# auto-discharge.net
KiCad netlist of a schematic drawn in Altium Designer
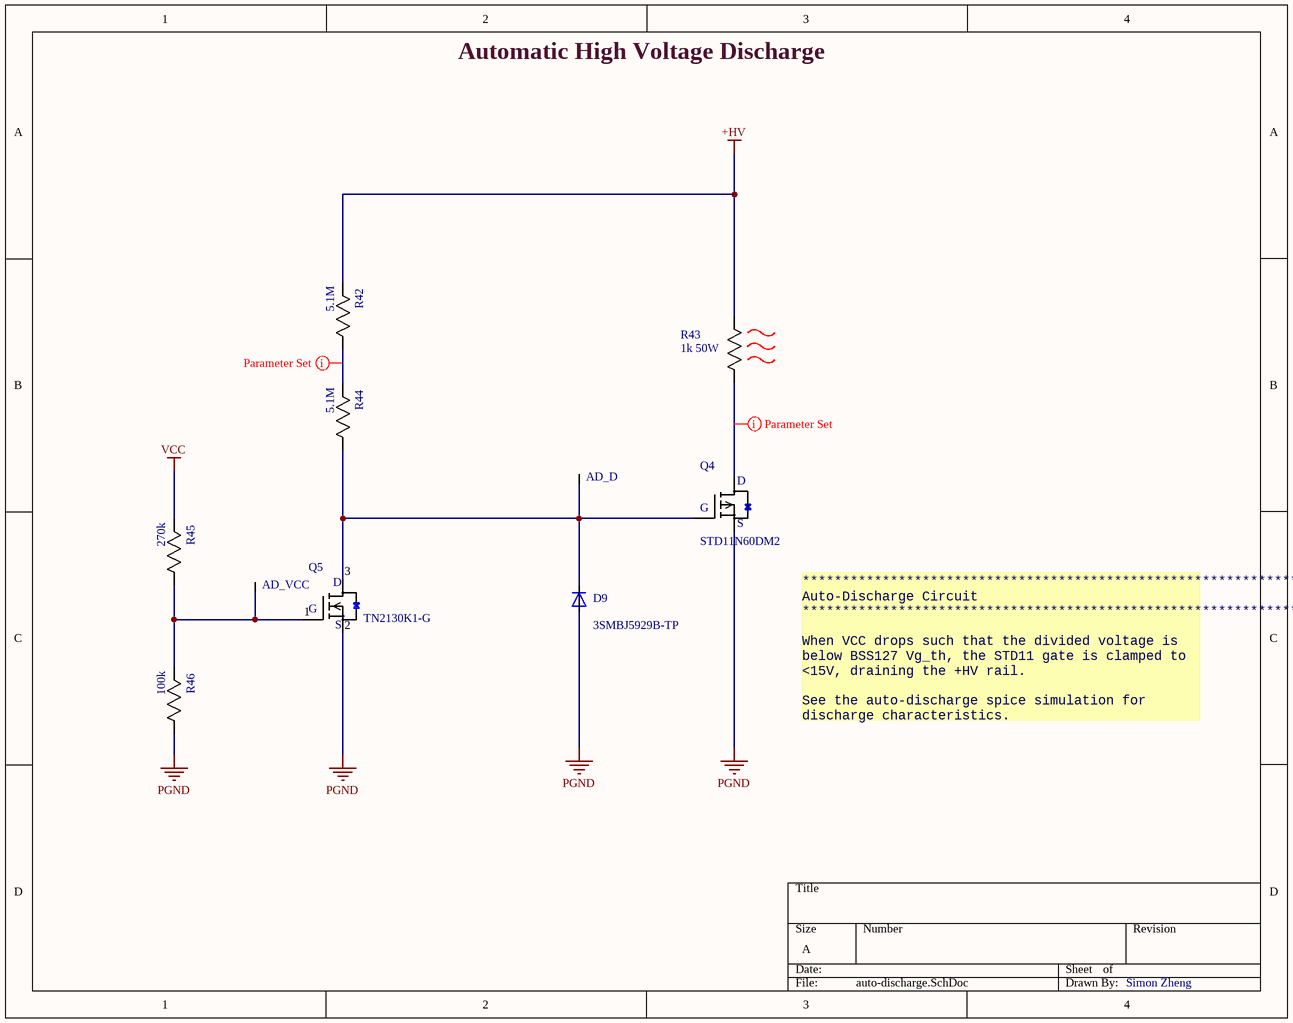
[diagram p0: auto-discharge.SchDoc]

(export (version "E")
  (design (tool "Eeschema 10.0.6"))
  (components
    (comp (ref "AD_D")
      (value "Test Point (Via)")
      (footprint "TP")
      (libsource (lib "IC_Library") (part "Test Point (Via)"))
    )
    (comp (ref "AD_VCC")
      (value "Test Point (Via)")
      (footprint "TP")
      (libsource (lib "IC_Library") (part "Test Point (Via)"))
    )
    (comp (ref "D9")
      (value "3SMBJ5929B-TP")
      (footprint "DO-214AA")
      (description "Diode ZENER 15V 3W")
      (fields (field (name "PART NUMBER") "DIODE ZENER 15V 3W"))
      (libsource (lib "Diode_Library") (part "DIODE ZENER 15V 3W"))
    )
    (comp (ref "Q4")
      (value "STD11N60DM2")
      (footprint "DPAK (TO-252)")
      (fields (field (name "MFG") "STMicroelectronics"))
      (libsource (lib "IC_Library") (part "STD11N60DM2"))
    )
    (comp (ref "Q5")
      (value "TN2130K1-G")
      (footprint "SOT95P237X112-3N")
      (description "N-Channel 300 V 85mA (Tj) 360mW (Tc) Surface Mount TO-236AB (SOT23)")
      (fields
        (field (name "PART NUMBER") "MOSFET N-CH TN2130K1-G")
        (field (name "COPYRIGHT") "Copyright (C) 2021 Ultra Librarian. All rights reserved.")
      )
      (libsource (lib "Transistor_Library") (part "MOSFET N-CH TN2130K1-G"))
    )
    (comp (ref "R42")
      (value "5.1M")
      (footprint "0603")
      (description "RES SMD 5.1 MOHM 5% 1/8W 0603")
      (fields (field (name "TOLERANCE") "5%") (field (name "PART NUMBER") "RES 5.1M 1/8W-5%"))
      (libsource (lib "") (part "RES 5.1M 1/8W-5%_1"))
    )
    (comp (ref "R43")
      (value "1k 50W")
      (footprint "D2PAK (TO-263)")
      (description "RES SMD 1.5K OHM 1% 50W D2PAK")
      (fields (field (name "TOLERANCE") "1%") (field (name "PART NUMBER") "RES 1.5k 50W"))
      (libsource (lib "Resistor_Library") (part "RES 1.5k 50W"))
    )
    (comp (ref "R44")
      (value "5.1M")
      (footprint "0603")
      (description "RES SMD 5.1 MOHM 5% 1/8W 0603")
      (fields (field (name "TOLERANCE") "5%") (field (name "PART NUMBER") "RES 5.1M 1/8W-5%"))
      (libsource (lib "Resistor_Library") (part "RES 5.1M 1/8W-5%"))
    )
    (comp (ref "R45")
      (value "270k")
      (footprint "0603")
      (description "RES SMD 270K OHM 5% 1/8W 0603")
      (fields (field (name "TOLERANCE") "5%") (field (name "PART NUMBER") "RES 270k 1/8W"))
      (libsource (lib "Resistor_Library") (part "RES 270k 1/8W"))
    )
    (comp (ref "R46")
      (value "100k")
      (footprint "0603")
      (description "RES SMD 100K OHM 1% 1/8W 0603")
      (fields (field (name "TOLERANCE") "1%") (field (name "PART NUMBER") "RES 100k 1/8W - 1%"))
      (libsource (lib "Resistor_Library") (part "RES 100k 1/8W 1%"))
    )
  )
  (nets
    (net (code "1") (name "+HV") (class "Default")
      (node (ref "R42") (pin "2") (pinfunction "R2_2") (pintype "passive"))
      (node (ref "R43") (pin "2") (pinfunction "R2_2") (pintype "passive"))
    )
    (net (code "2") (name "Net-(Q5-D)") (class "Default")
      (node (ref "AD_D") (pin "1") (pinfunction "1_1") (pintype "passive"))
      (node (ref "D9") (pin "C") (pinfunction "C_C") (pintype "passive"))
      (node (ref "Q4") (pin "G") (pinfunction "G_G") (pintype "passive"))
      (node (ref "Q5") (pin "3") (pinfunction "D_3") (pintype "passive"))
      (node (ref "R44") (pin "1") (pinfunction "R1_1") (pintype "passive"))
    )
    (net (code "3") (name "Net-(Q5-G)") (class "Default")
      (node (ref "AD_VCC") (pin "1") (pinfunction "1_1") (pintype "passive"))
      (node (ref "Q5") (pin "1") (pinfunction "G_1") (pintype "passive"))
      (node (ref "R45") (pin "1") (pinfunction "R1_1") (pintype "passive"))
      (node (ref "R46") (pin "2") (pinfunction "R2_2") (pintype "passive"))
    )
    (net (code "4") (name "Net-(R42-R1)") (class "Default")
      (node (ref "R42") (pin "1") (pinfunction "R1_1") (pintype "passive"))
      (node (ref "R44") (pin "2") (pinfunction "R2_2") (pintype "passive"))
    )
    (net (code "5") (name "Net-(R43-R1)") (class "Default")
      (node (ref "Q4") (pin "D") (pinfunction "D_D") (pintype "passive"))
      (node (ref "R43") (pin "1") (pinfunction "R1_1") (pintype "passive"))
    )
    (net (code "6") (name "PGND") (class "Default")
      (node (ref "D9") (pin "A") (pinfunction "A_A") (pintype "passive"))
      (node (ref "Q4") (pin "S") (pinfunction "S_S") (pintype "passive"))
      (node (ref "Q5") (pin "2") (pinfunction "S_2") (pintype "passive"))
      (node (ref "R46") (pin "1") (pinfunction "R1_1") (pintype "passive"))
    )
    (net (code "7") (name "VCC") (class "Default")
      (node (ref "R45") (pin "2") (pinfunction "R2_2") (pintype "passive"))
    )
    (net (code "8") (name "unconnected-(R43-Pad3)") (class "Default")
      (node (ref "R43") (pin "3") (pinfunction "3_3") (pintype "passive"))
    )
  )
)
